# Lanyard.net
KiCad netlist of a schematic drawn in EasyEDA Pro
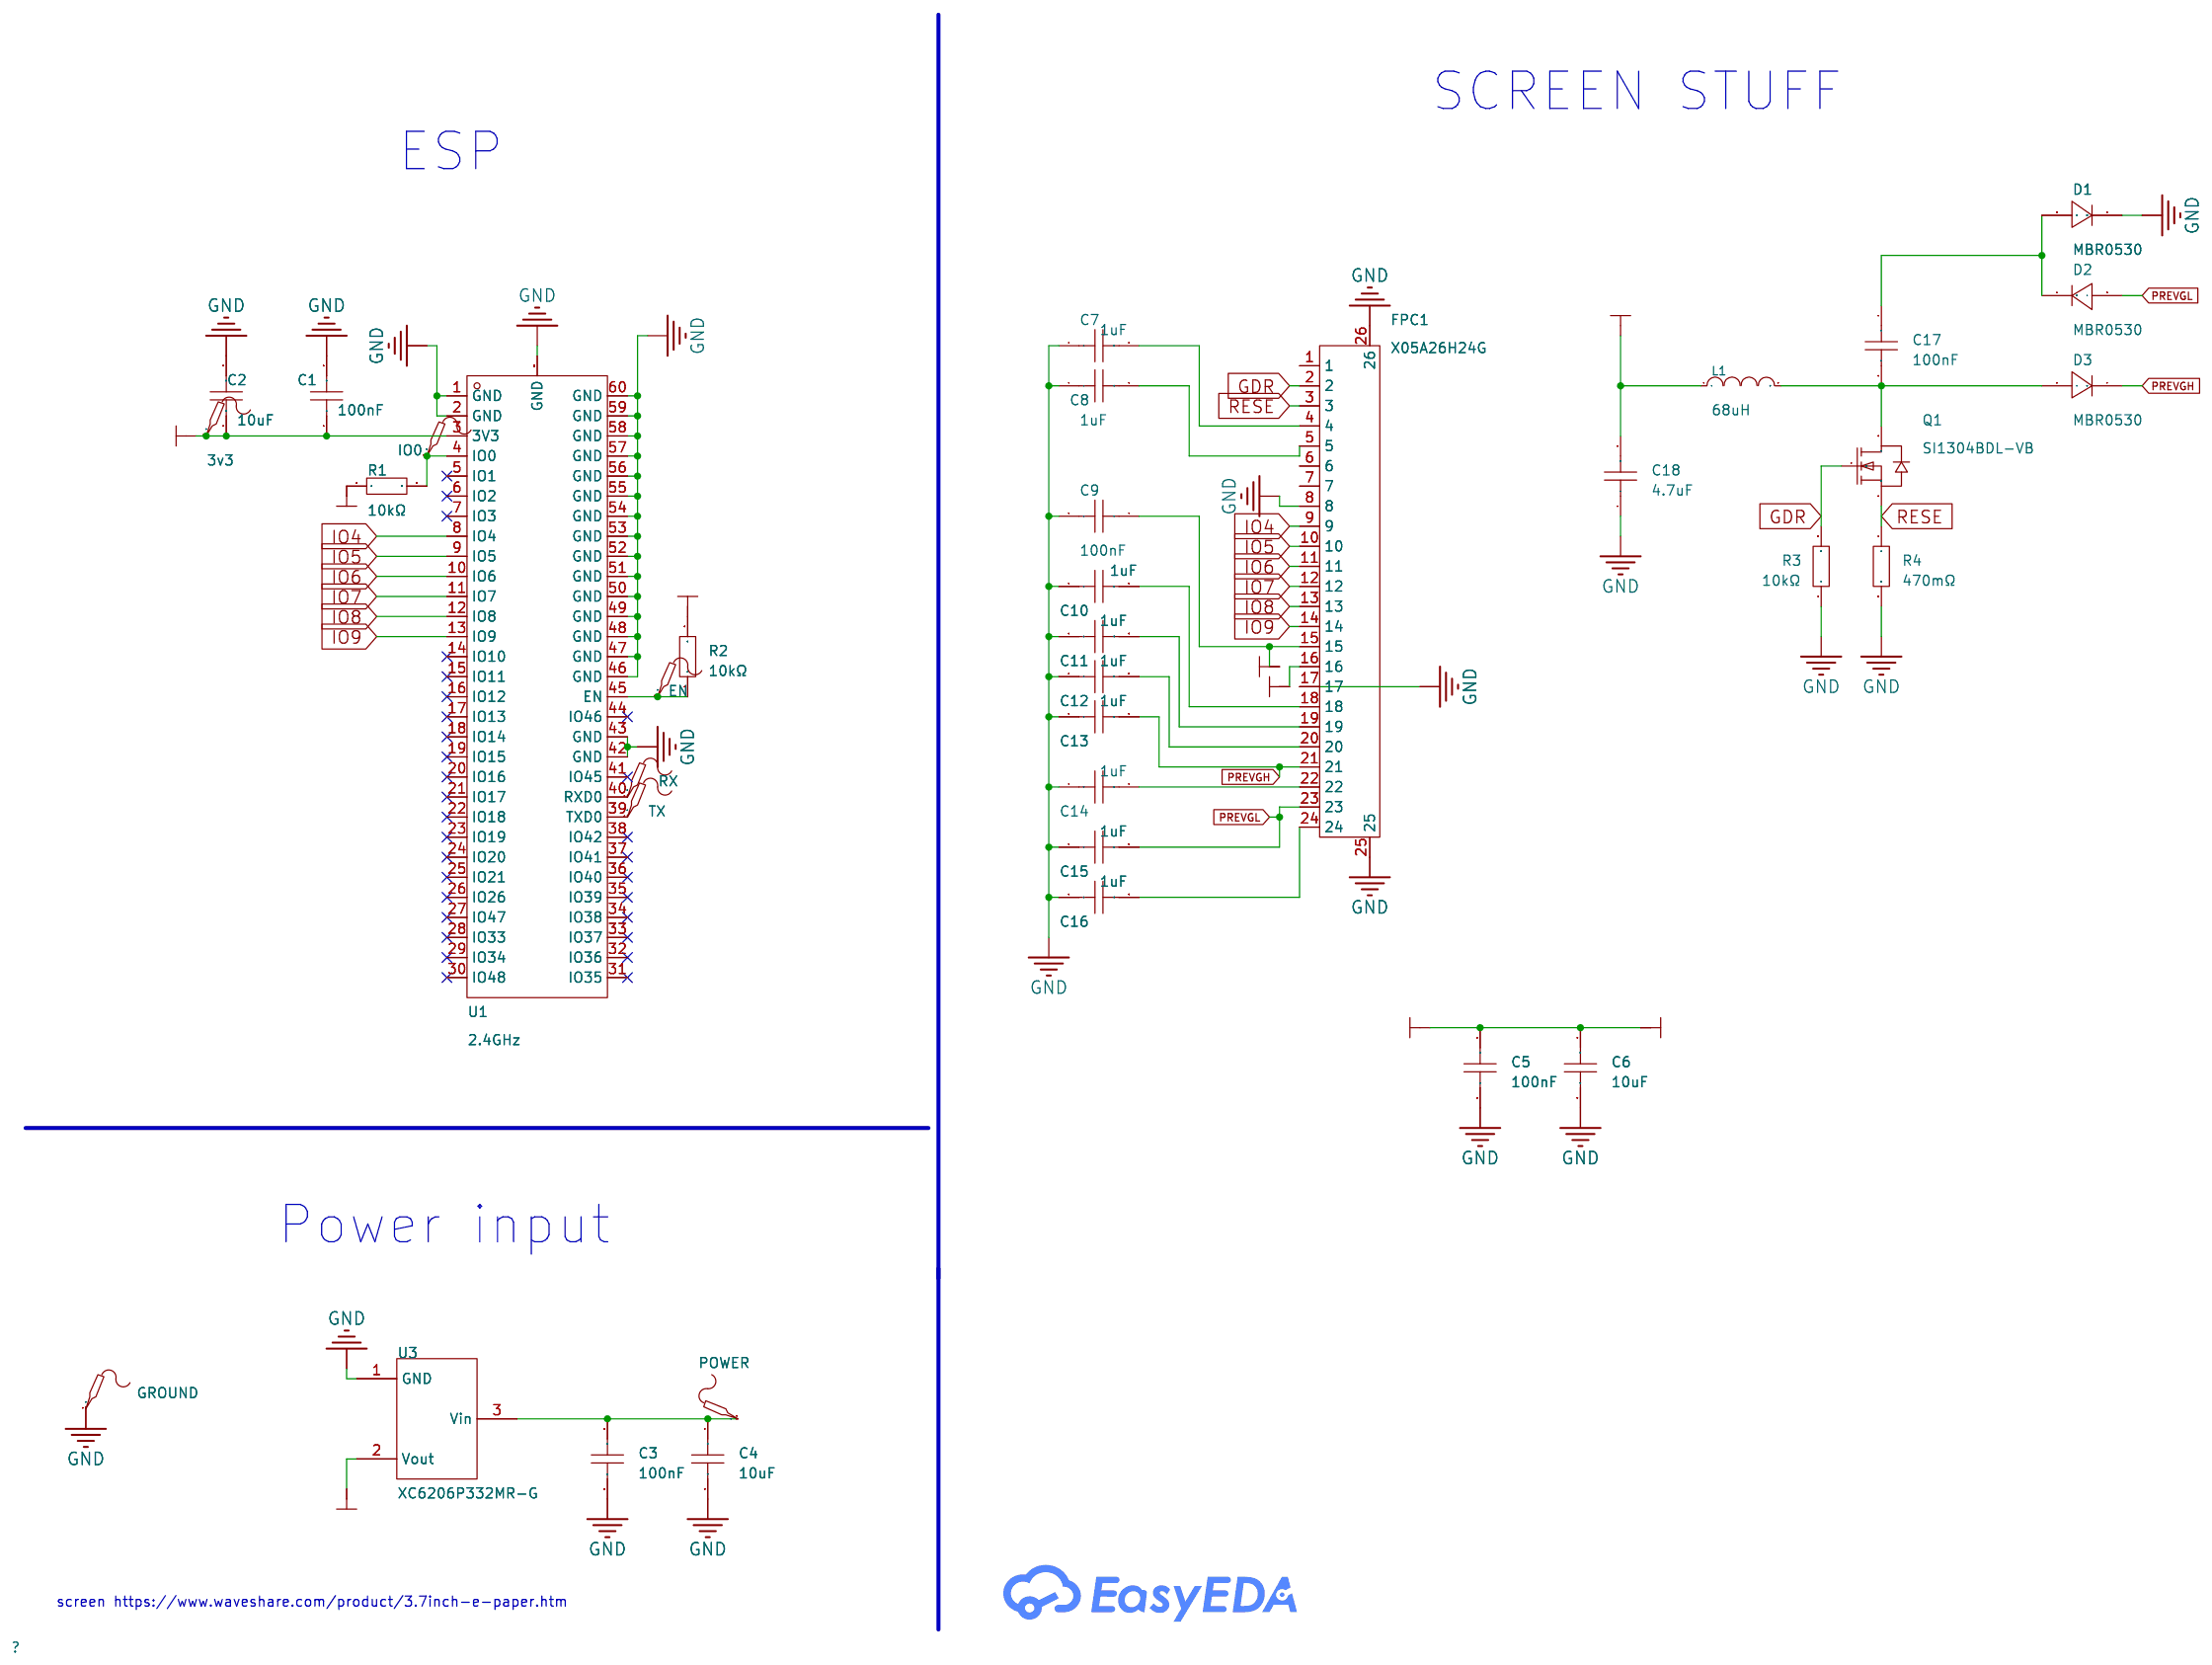
[diagram p0: schematic sheet]

(export (version "E")
  (design (tool "Eeschema 10.0.6"))
  (components
    (comp (ref "3v3")
      (value "~")
      (footprint "easyedapro:Test-Point-0.5mm")
      (description "Test Point 测试点")
      (libsource (lib "easyedapro") (part "Test-Point"))
    )
    (comp (ref "C1")
      (value "100nF")
      (footprint "easyedapro:C0603")
      (description "Capacitance:100nF Tolerance:±10% Tolerance:±10% Voltage Rating:50V Temperature Coefficient:X7R")
      (fields
        (field (name "Manufacturer Part") "CC0603KRX7R9BB104")
        (field (name "Manufacturer") "YAGEO(国巨)")
      )
      (libsource (lib "easyedapro") (part "CC0603KRX7R9BB104"))
    )
    (comp (ref "C2")
      (value "10uF")
      (footprint "easyedapro:C0603")
      (description "Capacitance:10uF Tolerance:±10% Tolerance:±10% Voltage Rating:10V Temperature Coefficient:X5R")
      (fields
        (field (name "Manufacturer Part") "CL10A106KP8NNNC")
        (field (name "Manufacturer") "SAMSUNG(三星)")
      )
      (libsource (lib "easyedapro") (part "CL10A106KP8NNNC"))
    )
    (comp (ref "C3")
      (value "100nF")
      (footprint "easyedapro:C0603")
      (description "Capacitance:100nF Tolerance:±10% Tolerance:±10% Voltage Rating:50V Temperature Coefficient:X7R")
      (fields
        (field (name "Manufacturer Part") "CC0603KRX7R9BB104")
        (field (name "Manufacturer") "YAGEO(国巨)")
      )
      (libsource (lib "easyedapro") (part "CC0603KRX7R9BB104"))
    )
    (comp (ref "C4")
      (value "10uF")
      (footprint "easyedapro:C0603")
      (description "Capacitance:10uF Tolerance:±10% Tolerance:±10% Voltage Rating:10V Temperature Coefficient:X5R")
      (fields
        (field (name "Manufacturer Part") "CL10A106KP8NNNC")
        (field (name "Manufacturer") "SAMSUNG(三星)")
      )
      (libsource (lib "easyedapro") (part "CL10A106KP8NNNC"))
    )
    (comp (ref "C5")
      (value "100nF")
      (footprint "easyedapro:C0603")
      (description "Capacitance:100nF Tolerance:±10% Tolerance:±10% Voltage Rating:50V Temperature Coefficient:X7R")
      (fields
        (field (name "Manufacturer Part") "CC0603KRX7R9BB104")
        (field (name "Manufacturer") "YAGEO(国巨)")
      )
      (libsource (lib "easyedapro") (part "CC0603KRX7R9BB104"))
    )
    (comp (ref "C6")
      (value "10uF")
      (footprint "easyedapro:C0603")
      (description "Capacitance:10uF Tolerance:±10% Tolerance:±10% Voltage Rating:10V Temperature Coefficient:X5R")
      (fields
        (field (name "Manufacturer Part") "CL10A106KP8NNNC")
        (field (name "Manufacturer") "SAMSUNG(三星)")
      )
      (libsource (lib "easyedapro") (part "CL10A106KP8NNNC"))
    )
    (comp (ref "C7")
      (value "1uF")
      (footprint "easyedapro:C0603")
      (description "Capacitance:1uF Tolerance:±10% Tolerance:±10% Voltage Rating:50V Temperature Coefficient:-")
      (fields
        (field (name "Manufacturer Part") "GRM188B31H105KAALD")
        (field (name "Manufacturer") "muRata(村田)")
      )
      (libsource (lib "easyedapro") (part "GRM188B31H105KAALD"))
    )
    (comp (ref "C8")
      (value "1uF")
      (footprint "easyedapro:C0603")
      (description "Capacitance:1uF Tolerance:±10% Tolerance:±10% Voltage Rating:50V Temperature Coefficient:-")
      (fields
        (field (name "Manufacturer Part") "GRM188B31H105KAALD")
        (field (name "Manufacturer") "muRata(村田)")
      )
      (libsource (lib "easyedapro") (part "GRM188B31H105KAALD"))
    )
    (comp (ref "C9")
      (value "100nF")
      (footprint "easyedapro:C0603")
      (description "Capacitance:100nF Tolerance:±10% Tolerance:±10% Voltage Rating:50V Temperature Coefficient:X7R")
      (fields
        (field (name "Manufacturer Part") "CC0603KRX7R9BB104")
        (field (name "Manufacturer") "YAGEO(国巨)")
      )
      (libsource (lib "easyedapro") (part "CC0603KRX7R9BB104"))
    )
    (comp (ref "C10")
      (value "1uF")
      (footprint "easyedapro:C0603")
      (description "Capacitance:1uF Tolerance:±10% Tolerance:±10% Voltage Rating:50V Temperature Coefficient:-")
      (fields
        (field (name "Manufacturer Part") "GRM188B31H105KAALD")
        (field (name "Manufacturer") "muRata(村田)")
      )
      (libsource (lib "easyedapro") (part "GRM188B31H105KAALD"))
    )
    (comp (ref "C11")
      (value "1uF")
      (footprint "easyedapro:C0603")
      (description "Capacitance:1uF Tolerance:±10% Tolerance:±10% Voltage Rating:50V Temperature Coefficient:-")
      (fields
        (field (name "Manufacturer Part") "GRM188B31H105KAALD")
        (field (name "Manufacturer") "muRata(村田)")
      )
      (libsource (lib "easyedapro") (part "GRM188B31H105KAALD"))
    )
    (comp (ref "C12")
      (value "1uF")
      (footprint "easyedapro:C0603")
      (description "Capacitance:1uF Tolerance:±10% Tolerance:±10% Voltage Rating:50V Temperature Coefficient:-")
      (fields
        (field (name "Manufacturer Part") "GRM188B31H105KAALD")
        (field (name "Manufacturer") "muRata(村田)")
      )
      (libsource (lib "easyedapro") (part "GRM188B31H105KAALD"))
    )
    (comp (ref "C13")
      (value "1uF")
      (footprint "easyedapro:C0603")
      (description "Capacitance:1uF Tolerance:±10% Tolerance:±10% Voltage Rating:50V Temperature Coefficient:-")
      (fields
        (field (name "Manufacturer Part") "GRM188B31H105KAALD")
        (field (name "Manufacturer") "muRata(村田)")
      )
      (libsource (lib "easyedapro") (part "GRM188B31H105KAALD"))
    )
    (comp (ref "C14")
      (value "1uF")
      (footprint "easyedapro:C0603")
      (description "Capacitance:1uF Tolerance:±10% Tolerance:±10% Voltage Rating:50V Temperature Coefficient:-")
      (fields
        (field (name "Manufacturer Part") "GRM188B31H105KAALD")
        (field (name "Manufacturer") "muRata(村田)")
      )
      (libsource (lib "easyedapro") (part "GRM188B31H105KAALD"))
    )
    (comp (ref "C15")
      (value "1uF")
      (footprint "easyedapro:C0603")
      (description "Capacitance:1uF Tolerance:±10% Tolerance:±10% Voltage Rating:50V Temperature Coefficient:-")
      (fields
        (field (name "Manufacturer Part") "GRM188B31H105KAALD")
        (field (name "Manufacturer") "muRata(村田)")
      )
      (libsource (lib "easyedapro") (part "GRM188B31H105KAALD"))
    )
    (comp (ref "C16")
      (value "1uF")
      (footprint "easyedapro:C0603")
      (description "Capacitance:1uF Tolerance:±10% Tolerance:±10% Voltage Rating:50V Temperature Coefficient:-")
      (fields
        (field (name "Manufacturer Part") "GRM188B31H105KAALD")
        (field (name "Manufacturer") "muRata(村田)")
      )
      (libsource (lib "easyedapro") (part "GRM188B31H105KAALD"))
    )
    (comp (ref "C17")
      (value "100nF")
      (footprint "easyedapro:C0603")
      (description "Capacitance:100nF Tolerance:±10% Tolerance:±10% Voltage Rating:50V Temperature Coefficient:X7R")
      (fields
        (field (name "Manufacturer Part") "CC0603KRX7R9BB104")
        (field (name "Manufacturer") "YAGEO(国巨)")
      )
      (libsource (lib "easyedapro") (part "CC0603KRX7R9BB104"))
    )
    (comp (ref "C18")
      (value "4.7uF")
      (footprint "easyedapro:C0603")
      (description "Capacitance:4.7uF Tolerance:±10% Tolerance:±10% Voltage Rating:16V Temperature Coefficient:X5R")
      (fields
        (field (name "Manufacturer Part") "CL10A475KO8NNNC")
        (field (name "Manufacturer") "SAMSUNG(三星)")
      )
      (libsource (lib "easyedapro") (part "CL10A475KO8NNNC"))
    )
    (comp (ref "D1")
      (value "MBR0530")
      (footprint "easyedapro:SOD-123_L2.8-W1.8-LS3.7-RD")
      (fields (field (name "Manufacturer") "CJ(江苏长电/长晶)"))
      (libsource (lib "easyedapro") (part "MBR0530"))
    )
    (comp (ref "D2")
      (value "MBR0530")
      (footprint "easyedapro:SOD-123_L2.8-W1.8-LS3.7-RD")
      (fields (field (name "Manufacturer") "CJ(江苏长电/长晶)"))
      (libsource (lib "easyedapro") (part "MBR0530"))
    )
    (comp (ref "D3")
      (value "MBR0530")
      (footprint "easyedapro:SOD-123_L2.8-W1.8-LS3.7-RD")
      (fields (field (name "Manufacturer") "CJ(江苏长电/长晶)"))
      (libsource (lib "easyedapro") (part "MBR0530"))
    )
    (comp (ref "EN")
      (value "~")
      (footprint "easyedapro:Test-Point-0.5mm")
      (description "Test Point 测试点")
      (libsource (lib "easyedapro") (part "Test-Point"))
    )
    (comp (ref "FPC1")
      (value "X05A26H24G")
      (footprint "easyedapro:FPC-SMD_X05A26H24G")
      (fields (field (name "Manufacturer") "XKB Connection(中国星坤)"))
      (libsource (lib "easyedapro") (part "X05A26H24G"))
    )
    (comp (ref "GROUND")
      (value "~")
      (footprint "easyedapro:Test-Point-0.5mm")
      (description "Test Point 测试点")
      (libsource (lib "easyedapro") (part "Test-Point"))
    )
    (comp (ref "IO0")
      (value "~")
      (footprint "easyedapro:Test-Point-0.5mm")
      (description "Test Point 测试点")
      (libsource (lib "easyedapro") (part "Test-Point"))
    )
    (comp (ref "L1")
      (value "68uH")
      (footprint "easyedapro:IND-SMD_L3.5-W3.0")
      (fields (field (name "Manufacturer Part") "SM3521-680MT") (field (name "Manufacturer") "SXN(顺翔诺)"))
      (libsource (lib "easyedapro") (part "SM3521-680MT"))
    )
    (comp (ref "POWER")
      (value "~")
      (footprint "easyedapro:Test-Point-0.5mm")
      (description "Test Point 测试点")
      (libsource (lib "easyedapro") (part "Test-Point"))
    )
    (comp (ref "Q1")
      (value "SI1304BDL-VB")
      (footprint "easyedapro:SC-70-3_L2.1-W1.3-P1.30-LS2.1-TL")
      (fields (field (name "Manufacturer") "VBsemi(微碧半导体)"))
      (libsource (lib "easyedapro") (part "SI1304BDL"))
    )
    (comp (ref "R1")
      (value "10kΩ")
      (footprint "easyedapro:R0603")
      (fields (field (name "Manufacturer Part") "RC0603FR-0710KL") (field (name "Manufacturer") "YAGEO(国巨)"))
      (libsource (lib "easyedapro") (part "RC0603FR-0710KL"))
    )
    (comp (ref "R2")
      (value "10kΩ")
      (footprint "easyedapro:R0603")
      (fields (field (name "Manufacturer Part") "RC0603FR-0710KL") (field (name "Manufacturer") "YAGEO(国巨)"))
      (libsource (lib "easyedapro") (part "RC0603FR-0710KL"))
    )
    (comp (ref "R3")
      (value "10kΩ")
      (footprint "easyedapro:R0603")
      (fields (field (name "Manufacturer Part") "RC0603FR-0710KL") (field (name "Manufacturer") "YAGEO(国巨)"))
      (libsource (lib "easyedapro") (part "RC0603FR-0710KL"))
    )
    (comp (ref "R4")
      (value "470mΩ")
      (footprint "easyedapro:R0603")
      (fields (field (name "Manufacturer Part") "SR731JTTDR470F") (field (name "Manufacturer") "KOA"))
      (libsource (lib "easyedapro") (part "SR731JTTDR470F"))
    )
    (comp (ref "RX")
      (value "~")
      (footprint "easyedapro:Test-Point-0.5mm")
      (description "Test Point 测试点")
      (libsource (lib "easyedapro") (part "Test-Point"))
    )
    (comp (ref "TX")
      (value "~")
      (footprint "easyedapro:Test-Point-0.5mm")
      (description "Test Point 测试点")
      (libsource (lib "easyedapro") (part "Test-Point"))
    )
    (comp (ref "U1")
      (value "2.4GHz")
      (footprint "easyedapro:BULETM-SMD_ESP32-S3-MINI-1-N8")
      (fields
        (field (name "Manufacturer Part") "ESP32-S3-MINI-1-N4R2")
        (field (name "Manufacturer") "ESPRESSIF(乐鑫)")
      )
      (libsource (lib "easyedapro") (part "ESP32-S3-MINI-1-N4R2"))
    )
    (comp (ref "U3")
      (value "XC6206P332MR-G")
      (footprint "easyedapro:SOT-23-3_L2.9-W1.6-P1.90-LS2.8-BR")
      (fields (field (name "Manufacturer") "TOREX(特瑞仕)"))
      (libsource (lib "easyedapro") (part "XC6206P332MR"))
    )
  )
  (nets
    (net (code "1") (name "3V3") (class "Default")
      (node (ref "3v3") (pin "1") (pinfunction "1_1") (pintype "unspecified"))
      (node (ref "C1") (pin "1") (pinfunction "1_1") (pintype "unspecified"))
      (node (ref "C18") (pin "2") (pinfunction "2_2") (pintype "unspecified"))
      (node (ref "C2") (pin "1") (pinfunction "1_1") (pintype "unspecified"))
      (node (ref "C5") (pin "1") (pinfunction "1_1") (pintype "unspecified"))
      (node (ref "C6") (pin "1") (pinfunction "1_1") (pintype "unspecified"))
      (node (ref "C9") (pin "1") (pinfunction "1_1") (pintype "unspecified"))
      (node (ref "FPC1") (pin "15") (pinfunction "15_15") (pintype "unspecified"))
      (node (ref "FPC1") (pin "16") (pinfunction "16_16") (pintype "unspecified"))
      (node (ref "L1") (pin "1") (pinfunction "1_1") (pintype "input"))
      (node (ref "R1") (pin "1") (pinfunction "1_1") (pintype "input"))
      (node (ref "R2") (pin "2") (pinfunction "2_2") (pintype "input"))
      (node (ref "U1") (pin "3") (pinfunction "3V3_3") (pintype "unspecified"))
      (node (ref "U3") (pin "2") (pinfunction "Vout_2") (pintype "unspecified"))
    )
    (net (code "2") (name "GDR") (class "Default")
      (node (ref "FPC1") (pin "2") (pinfunction "2_2") (pintype "unspecified"))
      (node (ref "Q1") (pin "1") (pinfunction "G_1") (pintype "unspecified"))
      (node (ref "R3") (pin "2") (pinfunction "2_2") (pintype "input"))
    )
    (net (code "3") (name "GND") (class "Default")
      (node (ref "C1") (pin "2") (pinfunction "2_2") (pintype "unspecified"))
      (node (ref "C10") (pin "1") (pinfunction "1_1") (pintype "unspecified"))
      (node (ref "C11") (pin "1") (pinfunction "1_1") (pintype "unspecified"))
      (node (ref "C12") (pin "1") (pinfunction "1_1") (pintype "unspecified"))
      (node (ref "C13") (pin "1") (pinfunction "1_1") (pintype "unspecified"))
      (node (ref "C14") (pin "1") (pinfunction "1_1") (pintype "unspecified"))
      (node (ref "C15") (pin "1") (pinfunction "1_1") (pintype "unspecified"))
      (node (ref "C16") (pin "1") (pinfunction "1_1") (pintype "unspecified"))
      (node (ref "C18") (pin "1") (pinfunction "1_1") (pintype "unspecified"))
      (node (ref "C2") (pin "2") (pinfunction "2_2") (pintype "unspecified"))
      (node (ref "C3") (pin "2") (pinfunction "2_2") (pintype "unspecified"))
      (node (ref "C4") (pin "2") (pinfunction "2_2") (pintype "unspecified"))
      (node (ref "C5") (pin "2") (pinfunction "2_2") (pintype "unspecified"))
      (node (ref "C6") (pin "2") (pinfunction "2_2") (pintype "unspecified"))
      (node (ref "C7") (pin "1") (pinfunction "1_1") (pintype "unspecified"))
      (node (ref "C8") (pin "1") (pinfunction "1_1") (pintype "unspecified"))
      (node (ref "C9") (pin "2") (pinfunction "2_2") (pintype "unspecified"))
      (node (ref "D1") (pin "1") (pinfunction "C_1") (pintype "unspecified"))
      (node (ref "FPC1") (pin "17") (pinfunction "17_17") (pintype "unspecified"))
      (node (ref "FPC1") (pin "25") (pinfunction "25_25") (pintype "unspecified"))
      (node (ref "FPC1") (pin "26") (pinfunction "26_26") (pintype "unspecified"))
      (node (ref "FPC1") (pin "8") (pinfunction "8_8") (pintype "unspecified"))
      (node (ref "GROUND") (pin "1") (pinfunction "1_1") (pintype "unspecified"))
      (node (ref "R3") (pin "1") (pinfunction "1_1") (pintype "input"))
      (node (ref "R4") (pin "2") (pinfunction "2_2") (pintype "unspecified"))
      (node (ref "U1") (pin "1") (pinfunction "GND_1") (pintype "unspecified"))
      (node (ref "U1") (pin "2") (pinfunction "GND_2") (pintype "unspecified"))
      (node (ref "U1") (pin "42") (pinfunction "GND_42") (pintype "unspecified"))
      (node (ref "U1") (pin "43") (pinfunction "GND_43") (pintype "unspecified"))
      (node (ref "U1") (pin "46") (pinfunction "GND_46") (pintype "unspecified"))
      (node (ref "U1") (pin "47") (pinfunction "GND_47") (pintype "unspecified"))
      (node (ref "U1") (pin "48") (pinfunction "GND_48") (pintype "unspecified"))
      (node (ref "U1") (pin "49") (pinfunction "GND_49") (pintype "unspecified"))
      (node (ref "U1") (pin "50") (pinfunction "GND_50") (pintype "unspecified"))
      (node (ref "U1") (pin "51") (pinfunction "GND_51") (pintype "unspecified"))
      (node (ref "U1") (pin "52") (pinfunction "GND_52") (pintype "unspecified"))
      (node (ref "U1") (pin "53") (pinfunction "GND_53") (pintype "unspecified"))
      (node (ref "U1") (pin "54") (pinfunction "GND_54") (pintype "unspecified"))
      (node (ref "U1") (pin "55") (pinfunction "GND_55") (pintype "unspecified"))
      (node (ref "U1") (pin "56") (pinfunction "GND_56") (pintype "unspecified"))
      (node (ref "U1") (pin "57") (pinfunction "GND_57") (pintype "unspecified"))
      (node (ref "U1") (pin "58") (pinfunction "GND_58") (pintype "unspecified"))
      (node (ref "U1") (pin "59") (pinfunction "GND_59") (pintype "unspecified"))
      (node (ref "U1") (pin "60") (pinfunction "GND_60") (pintype "unspecified"))
      (node (ref "U1") (pin "GND") (pinfunction "GND_GND") (pintype "unspecified"))
      (node (ref "U3") (pin "1") (pinfunction "GND_1") (pintype "unspecified"))
    )
    (net (code "4") (name "IO4") (class "Default")
      (node (ref "FPC1") (pin "9") (pinfunction "9_9") (pintype "unspecified"))
      (node (ref "U1") (pin "8") (pinfunction "IO4_8") (pintype "unspecified"))
    )
    (net (code "5") (name "IO5") (class "Default")
      (node (ref "FPC1") (pin "10") (pinfunction "10_10") (pintype "unspecified"))
      (node (ref "U1") (pin "9") (pinfunction "IO5_9") (pintype "unspecified"))
    )
    (net (code "6") (name "IO6") (class "Default")
      (node (ref "FPC1") (pin "11") (pinfunction "11_11") (pintype "unspecified"))
      (node (ref "U1") (pin "10") (pinfunction "IO6_10") (pintype "unspecified"))
    )
    (net (code "7") (name "IO7") (class "Default")
      (node (ref "FPC1") (pin "12") (pinfunction "12_12") (pintype "unspecified"))
      (node (ref "U1") (pin "11") (pinfunction "IO7_11") (pintype "unspecified"))
    )
    (net (code "8") (name "IO8") (class "Default")
      (node (ref "FPC1") (pin "13") (pinfunction "13_13") (pintype "unspecified"))
      (node (ref "U1") (pin "12") (pinfunction "IO8_12") (pintype "unspecified"))
    )
    (net (code "9") (name "IO9") (class "Default")
      (node (ref "FPC1") (pin "14") (pinfunction "14_14") (pintype "unspecified"))
      (node (ref "U1") (pin "13") (pinfunction "IO9_13") (pintype "unspecified"))
    )
    (net (code "10") (name "Net-(C7-Pad2)") (class "Default")
      (node (ref "C7") (pin "2") (pinfunction "2_2") (pintype "unspecified"))
      (node (ref "FPC1") (pin "4") (pinfunction "4_4") (pintype "unspecified"))
    )
    (net (code "11") (name "Net-(C8-Pad2)") (class "Default")
      (node (ref "C8") (pin "2") (pinfunction "2_2") (pintype "unspecified"))
      (node (ref "FPC1") (pin "5") (pinfunction "5_5") (pintype "unspecified"))
    )
    (net (code "12") (name "Net-(C10-Pad2)") (class "Default")
      (node (ref "C10") (pin "2") (pinfunction "2_2") (pintype "unspecified"))
      (node (ref "FPC1") (pin "18") (pinfunction "18_18") (pintype "unspecified"))
    )
    (net (code "13") (name "Net-(C11-Pad2)") (class "Default")
      (node (ref "C11") (pin "2") (pinfunction "2_2") (pintype "unspecified"))
      (node (ref "FPC1") (pin "19") (pinfunction "19_19") (pintype "unspecified"))
    )
    (net (code "14") (name "Net-(C12-Pad2)") (class "Default")
      (node (ref "C12") (pin "2") (pinfunction "2_2") (pintype "unspecified"))
      (node (ref "FPC1") (pin "20") (pinfunction "20_20") (pintype "unspecified"))
    )
    (net (code "15") (name "Net-(C14-Pad2)") (class "Default")
      (node (ref "C14") (pin "2") (pinfunction "2_2") (pintype "unspecified"))
      (node (ref "FPC1") (pin "22") (pinfunction "22_22") (pintype "unspecified"))
    )
    (net (code "16") (name "Net-(C16-Pad2)") (class "Default")
      (node (ref "C16") (pin "2") (pinfunction "2_2") (pintype "unspecified"))
      (node (ref "FPC1") (pin "24") (pinfunction "24_24") (pintype "unspecified"))
    )
    (net (code "17") (name "Net-(D1-A)") (class "Default")
      (node (ref "C17") (pin "1") (pinfunction "1_1") (pintype "unspecified"))
      (node (ref "D1") (pin "2") (pinfunction "A_2") (pintype "unspecified"))
      (node (ref "D2") (pin "1") (pinfunction "C_1") (pintype "unspecified"))
    )
    (net (code "18") (name "Net-(D3-A)") (class "Default")
      (node (ref "C17") (pin "2") (pinfunction "2_2") (pintype "unspecified"))
      (node (ref "D3") (pin "2") (pinfunction "A_2") (pintype "unspecified"))
      (node (ref "L1") (pin "2") (pinfunction "2_2") (pintype "input"))
      (node (ref "Q1") (pin "3") (pinfunction "D_3") (pintype "unspecified"))
    )
    (net (code "19") (name "Net-(U1-EN)") (class "Default")
      (node (ref "EN") (pin "1") (pinfunction "1_1") (pintype "unspecified"))
      (node (ref "R2") (pin "1") (pinfunction "1_1") (pintype "input"))
      (node (ref "U1") (pin "45") (pinfunction "EN_45") (pintype "unspecified"))
    )
    (net (code "20") (name "Net-(U1-IO0)") (class "Default")
      (node (ref "IO0") (pin "1") (pinfunction "1_1") (pintype "unspecified"))
      (node (ref "R1") (pin "2") (pinfunction "2_2") (pintype "input"))
      (node (ref "U1") (pin "4") (pinfunction "IO0_4") (pintype "unspecified"))
    )
    (net (code "21") (name "Net-(U1-RXD0)") (class "Default")
      (node (ref "RX") (pin "1") (pinfunction "1_1") (pintype "unspecified"))
      (node (ref "U1") (pin "40") (pinfunction "RXD0_40") (pintype "unspecified"))
    )
    (net (code "22") (name "Net-(U1-TXD0)") (class "Default")
      (node (ref "TX") (pin "1") (pinfunction "1_1") (pintype "unspecified"))
      (node (ref "U1") (pin "39") (pinfunction "TXD0_39") (pintype "unspecified"))
    )
    (net (code "23") (name "Net-(U3-Vin)") (class "Default")
      (node (ref "C3") (pin "1") (pinfunction "1_1") (pintype "unspecified"))
      (node (ref "C4") (pin "1") (pinfunction "1_1") (pintype "unspecified"))
      (node (ref "POWER") (pin "1") (pinfunction "1_1") (pintype "unspecified"))
      (node (ref "U3") (pin "3") (pinfunction "Vin_3") (pintype "unspecified"))
    )
    (net (code "24") (name "PREVGH") (class "Default")
      (node (ref "C13") (pin "2") (pinfunction "2_2") (pintype "unspecified"))
      (node (ref "D3") (pin "1") (pinfunction "C_1") (pintype "unspecified"))
      (node (ref "FPC1") (pin "21") (pinfunction "21_21") (pintype "unspecified"))
    )
    (net (code "25") (name "PREVGL") (class "Default")
      (node (ref "C15") (pin "2") (pinfunction "2_2") (pintype "unspecified"))
      (node (ref "D2") (pin "2") (pinfunction "A_2") (pintype "unspecified"))
      (node (ref "FPC1") (pin "23") (pinfunction "23_23") (pintype "unspecified"))
    )
    (net (code "26") (name "RESE") (class "Default")
      (node (ref "FPC1") (pin "3") (pinfunction "3_3") (pintype "unspecified"))
      (node (ref "Q1") (pin "2") (pinfunction "S_2") (pintype "unspecified"))
      (node (ref "R4") (pin "1") (pinfunction "1_1") (pintype "unspecified"))
    )
    (net (code "27") (name "unconnected-(FPC1-Pad1)") (class "Default")
      (node (ref "FPC1") (pin "1") (pinfunction "1_1") (pintype "unspecified"))
    )
    (net (code "28") (name "unconnected-(FPC1-Pad6)") (class "Default")
      (node (ref "FPC1") (pin "6") (pinfunction "6_6") (pintype "unspecified"))
    )
    (net (code "29") (name "unconnected-(FPC1-Pad7)") (class "Default")
      (node (ref "FPC1") (pin "7") (pinfunction "7_7") (pintype "unspecified"))
    )
    (net (code "30") (name "unconnected-(U1-IO1-Pad5)") (class "Default")
      (node (ref "U1") (pin "5") (pinfunction "IO1_5") (pintype "unspecified+no_connect"))
    )
    (net (code "31") (name "unconnected-(U1-IO2-Pad6)") (class "Default")
      (node (ref "U1") (pin "6") (pinfunction "IO2_6") (pintype "unspecified+no_connect"))
    )
    (net (code "32") (name "unconnected-(U1-IO3-Pad7)") (class "Default")
      (node (ref "U1") (pin "7") (pinfunction "IO3_7") (pintype "unspecified+no_connect"))
    )
    (net (code "33") (name "unconnected-(U1-IO10-Pad14)") (class "Default")
      (node (ref "U1") (pin "14") (pinfunction "IO10_14") (pintype "unspecified+no_connect"))
    )
    (net (code "34") (name "unconnected-(U1-IO11-Pad15)") (class "Default")
      (node (ref "U1") (pin "15") (pinfunction "IO11_15") (pintype "unspecified+no_connect"))
    )
    (net (code "35") (name "unconnected-(U1-IO12-Pad16)") (class "Default")
      (node (ref "U1") (pin "16") (pinfunction "IO12_16") (pintype "unspecified+no_connect"))
    )
    (net (code "36") (name "unconnected-(U1-IO13-Pad17)") (class "Default")
      (node (ref "U1") (pin "17") (pinfunction "IO13_17") (pintype "unspecified+no_connect"))
    )
    (net (code "37") (name "unconnected-(U1-IO14-Pad18)") (class "Default")
      (node (ref "U1") (pin "18") (pinfunction "IO14_18") (pintype "unspecified+no_connect"))
    )
    (net (code "38") (name "unconnected-(U1-IO15-Pad19)") (class "Default")
      (node (ref "U1") (pin "19") (pinfunction "IO15_19") (pintype "unspecified+no_connect"))
    )
    (net (code "39") (name "unconnected-(U1-IO16-Pad20)") (class "Default")
      (node (ref "U1") (pin "20") (pinfunction "IO16_20") (pintype "unspecified+no_connect"))
    )
    (net (code "40") (name "unconnected-(U1-IO17-Pad21)") (class "Default")
      (node (ref "U1") (pin "21") (pinfunction "IO17_21") (pintype "unspecified+no_connect"))
    )
    (net (code "41") (name "unconnected-(U1-IO18-Pad22)") (class "Default")
      (node (ref "U1") (pin "22") (pinfunction "IO18_22") (pintype "unspecified+no_connect"))
    )
    (net (code "42") (name "unconnected-(U1-IO19-Pad23)") (class "Default")
      (node (ref "U1") (pin "23") (pinfunction "IO19_23") (pintype "unspecified+no_connect"))
    )
    (net (code "43") (name "unconnected-(U1-IO20-Pad24)") (class "Default")
      (node (ref "U1") (pin "24") (pinfunction "IO20_24") (pintype "unspecified+no_connect"))
    )
    (net (code "44") (name "unconnected-(U1-IO21-Pad25)") (class "Default")
      (node (ref "U1") (pin "25") (pinfunction "IO21_25") (pintype "unspecified+no_connect"))
    )
    (net (code "45") (name "unconnected-(U1-IO26-Pad26)") (class "Default")
      (node (ref "U1") (pin "26") (pinfunction "IO26_26") (pintype "unspecified+no_connect"))
    )
    (net (code "46") (name "unconnected-(U1-IO33-Pad28)") (class "Default")
      (node (ref "U1") (pin "28") (pinfunction "IO33_28") (pintype "unspecified+no_connect"))
    )
    (net (code "47") (name "unconnected-(U1-IO34-Pad29)") (class "Default")
      (node (ref "U1") (pin "29") (pinfunction "IO34_29") (pintype "unspecified+no_connect"))
    )
    (net (code "48") (name "unconnected-(U1-IO35-Pad31)") (class "Default")
      (node (ref "U1") (pin "31") (pinfunction "IO35_31") (pintype "unspecified+no_connect"))
    )
    (net (code "49") (name "unconnected-(U1-IO36-Pad32)") (class "Default")
      (node (ref "U1") (pin "32") (pinfunction "IO36_32") (pintype "unspecified+no_connect"))
    )
    (net (code "50") (name "unconnected-(U1-IO37-Pad33)") (class "Default")
      (node (ref "U1") (pin "33") (pinfunction "IO37_33") (pintype "unspecified+no_connect"))
    )
    (net (code "51") (name "unconnected-(U1-IO38-Pad34)") (class "Default")
      (node (ref "U1") (pin "34") (pinfunction "IO38_34") (pintype "unspecified+no_connect"))
    )
    (net (code "52") (name "unconnected-(U1-IO39-Pad35)") (class "Default")
      (node (ref "U1") (pin "35") (pinfunction "IO39_35") (pintype "unspecified+no_connect"))
    )
    (net (code "53") (name "unconnected-(U1-IO40-Pad36)") (class "Default")
      (node (ref "U1") (pin "36") (pinfunction "IO40_36") (pintype "unspecified+no_connect"))
    )
    (net (code "54") (name "unconnected-(U1-IO41-Pad37)") (class "Default")
      (node (ref "U1") (pin "37") (pinfunction "IO41_37") (pintype "unspecified+no_connect"))
    )
    (net (code "55") (name "unconnected-(U1-IO42-Pad38)") (class "Default")
      (node (ref "U1") (pin "38") (pinfunction "IO42_38") (pintype "unspecified+no_connect"))
    )
    (net (code "56") (name "unconnected-(U1-IO45-Pad41)") (class "Default")
      (node (ref "U1") (pin "41") (pinfunction "IO45_41") (pintype "unspecified+no_connect"))
    )
    (net (code "57") (name "unconnected-(U1-IO46-Pad44)") (class "Default")
      (node (ref "U1") (pin "44") (pinfunction "IO46_44") (pintype "unspecified+no_connect"))
    )
    (net (code "58") (name "unconnected-(U1-IO47-Pad27)") (class "Default")
      (node (ref "U1") (pin "27") (pinfunction "IO47_27") (pintype "unspecified+no_connect"))
    )
    (net (code "59") (name "unconnected-(U1-IO48-Pad30)") (class "Default")
      (node (ref "U1") (pin "30") (pinfunction "IO48_30") (pintype "unspecified+no_connect"))
    )
  )
)
